# Bridge_Schem.net
KiCad netlist of a schematic drawn in Altium Designer
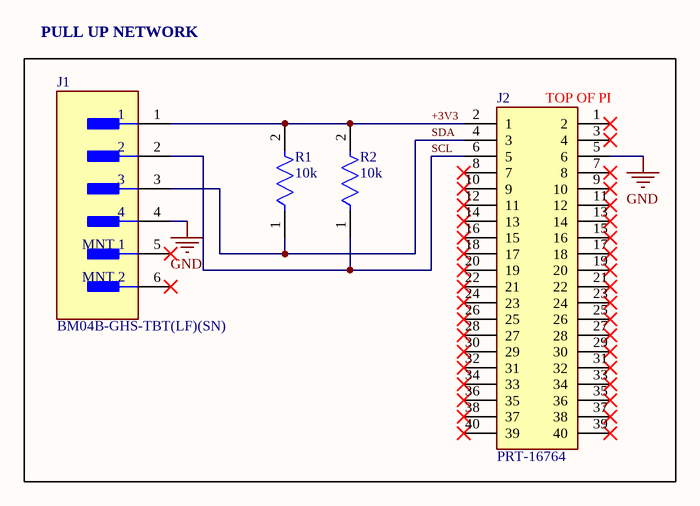
[diagram p0: Bridge_Schem.SchDoc]

(export (version "E")
  (design (tool "Eeschema 10.0.6"))
  (components
    (comp (ref "J1")
      (value "BM04B-GHS-TBT(LF)(SN)")
      (footprint "FP-BM04B-GHS-TBT_LF_SN-MFG")
      (description "CONN HEADER SMD 4POS 1.25MM")
      (fields (field (name "CHECK CONNECTOR") "Pending"))
      (libsource (lib "Altium Content Vault") (part "8e3688c4b118bffc0dd9b7401e414ba"))
    )
    (comp (ref "J2")
      (value "PRT-16764")
      (footprint "SamacSys:RHDR40W64P254_2X20_5130X500X1375P")
      (description "Connector")
      (fields (field (name "MOUSER PART NUMBER") "474-PRT-16764"))
      (libsource (lib "*") (part "PRT-16764"))
    )
    (comp (ref "R1")
      (value "10k")
      (footprint "FP-AT0805-MFG")
      (description "Thin Film Chip Resistors Automotive Grade 10kΩ 0.5% 50ppm/°C 0805")
      (fields (field (name "TOLERANCE") "0.5%"))
      (libsource (lib "Altium Content Vault") (part "1029c3af85768c4190bb7ad29bc67b5"))
    )
    (comp (ref "R2")
      (value "10k")
      (footprint "FP-AT0805-MFG")
      (description "Thin Film Chip Resistors Automotive Grade 10kΩ 0.5% 50ppm/°C 0805")
      (fields (field (name "TOLERANCE") "0.5%"))
      (libsource (lib "Altium Content Vault") (part "1029c3af85768c4190bb7ad29bc67b5"))
    )
  )
  (nets
    (net (code "1") (name "/+3V3") (class "Default")
      (node (ref "J1") (pin "1") (pinfunction "1_1") (pintype "passive"))
      (node (ref "J2") (pin "2") (pinfunction "1_2") (pintype "passive"))
      (node (ref "R1") (pin "2") (pinfunction "2_2") (pintype "passive"))
      (node (ref "R2") (pin "2") (pinfunction "2_2") (pintype "passive"))
    )
    (net (code "2") (name "/SCL") (class "Default")
      (node (ref "J1") (pin "2") (pinfunction "2_2") (pintype "passive"))
      (node (ref "J2") (pin "6") (pinfunction "5_6") (pintype "passive"))
      (node (ref "R2") (pin "1") (pinfunction "1_1") (pintype "passive"))
    )
    (net (code "3") (name "/SDA") (class "Default")
      (node (ref "J1") (pin "3") (pinfunction "3_3") (pintype "passive"))
      (node (ref "J2") (pin "4") (pinfunction "3_4") (pintype "passive"))
      (node (ref "R1") (pin "1") (pinfunction "1_1") (pintype "passive"))
    )
    (net (code "4") (name "GND") (class "Default")
      (node (ref "J1") (pin "4") (pinfunction "4_4") (pintype "passive"))
      (node (ref "J2") (pin "5") (pinfunction "6_5") (pintype "passive"))
    )
    (net (code "5") (name "unconnected-(J1-MNT_1-Pad5)") (class "Default")
      (node (ref "J1") (pin "5") (pinfunction "MNT_1_5") (pintype "passive+no_connect"))
    )
    (net (code "6") (name "unconnected-(J1-MNT_2-Pad6)") (class "Default")
      (node (ref "J1") (pin "6") (pinfunction "MNT_2_6") (pintype "passive+no_connect"))
    )
    (net (code "7") (name "unconnected-(J2-2-Pad1)") (class "Default")
      (node (ref "J2") (pin "1") (pinfunction "2_1") (pintype "passive+no_connect"))
    )
    (net (code "8") (name "unconnected-(J2-4-Pad3)") (class "Default")
      (node (ref "J2") (pin "3") (pinfunction "4_3") (pintype "passive+no_connect"))
    )
    (net (code "9") (name "unconnected-(J2-7-Pad8)") (class "Default")
      (node (ref "J2") (pin "8") (pinfunction "7_8") (pintype "passive+no_connect"))
    )
    (net (code "10") (name "unconnected-(J2-8-Pad7)") (class "Default")
      (node (ref "J2") (pin "7") (pinfunction "8_7") (pintype "passive+no_connect"))
    )
    (net (code "11") (name "unconnected-(J2-9-Pad10)") (class "Default")
      (node (ref "J2") (pin "10") (pinfunction "9_10") (pintype "passive+no_connect"))
    )
    (net (code "12") (name "unconnected-(J2-10-Pad9)") (class "Default")
      (node (ref "J2") (pin "9") (pinfunction "10_9") (pintype "passive+no_connect"))
    )
    (net (code "13") (name "unconnected-(J2-11-Pad12)") (class "Default")
      (node (ref "J2") (pin "12") (pinfunction "11_12") (pintype "passive+no_connect"))
    )
    (net (code "14") (name "unconnected-(J2-12-Pad11)") (class "Default")
      (node (ref "J2") (pin "11") (pinfunction "12_11") (pintype "passive+no_connect"))
    )
    (net (code "15") (name "unconnected-(J2-13-Pad14)") (class "Default")
      (node (ref "J2") (pin "14") (pinfunction "13_14") (pintype "passive+no_connect"))
    )
    (net (code "16") (name "unconnected-(J2-14-Pad13)") (class "Default")
      (node (ref "J2") (pin "13") (pinfunction "14_13") (pintype "passive+no_connect"))
    )
    (net (code "17") (name "unconnected-(J2-15-Pad16)") (class "Default")
      (node (ref "J2") (pin "16") (pinfunction "15_16") (pintype "passive+no_connect"))
    )
    (net (code "18") (name "unconnected-(J2-16-Pad15)") (class "Default")
      (node (ref "J2") (pin "15") (pinfunction "16_15") (pintype "passive+no_connect"))
    )
    (net (code "19") (name "unconnected-(J2-17-Pad18)") (class "Default")
      (node (ref "J2") (pin "18") (pinfunction "17_18") (pintype "passive+no_connect"))
    )
    (net (code "20") (name "unconnected-(J2-18-Pad17)") (class "Default")
      (node (ref "J2") (pin "17") (pinfunction "18_17") (pintype "passive+no_connect"))
    )
    (net (code "21") (name "unconnected-(J2-19-Pad20)") (class "Default")
      (node (ref "J2") (pin "20") (pinfunction "19_20") (pintype "passive+no_connect"))
    )
    (net (code "22") (name "unconnected-(J2-20-Pad19)") (class "Default")
      (node (ref "J2") (pin "19") (pinfunction "20_19") (pintype "passive+no_connect"))
    )
    (net (code "23") (name "unconnected-(J2-21-Pad22)") (class "Default")
      (node (ref "J2") (pin "22") (pinfunction "21_22") (pintype "passive+no_connect"))
    )
    (net (code "24") (name "unconnected-(J2-22-Pad21)") (class "Default")
      (node (ref "J2") (pin "21") (pinfunction "22_21") (pintype "passive+no_connect"))
    )
    (net (code "25") (name "unconnected-(J2-23-Pad24)") (class "Default")
      (node (ref "J2") (pin "24") (pinfunction "23_24") (pintype "passive+no_connect"))
    )
    (net (code "26") (name "unconnected-(J2-24-Pad23)") (class "Default")
      (node (ref "J2") (pin "23") (pinfunction "24_23") (pintype "passive+no_connect"))
    )
    (net (code "27") (name "unconnected-(J2-25-Pad26)") (class "Default")
      (node (ref "J2") (pin "26") (pinfunction "25_26") (pintype "passive+no_connect"))
    )
    (net (code "28") (name "unconnected-(J2-26-Pad25)") (class "Default")
      (node (ref "J2") (pin "25") (pinfunction "26_25") (pintype "passive+no_connect"))
    )
    (net (code "29") (name "unconnected-(J2-27-Pad28)") (class "Default")
      (node (ref "J2") (pin "28") (pinfunction "27_28") (pintype "passive+no_connect"))
    )
    (net (code "30") (name "unconnected-(J2-28-Pad27)") (class "Default")
      (node (ref "J2") (pin "27") (pinfunction "28_27") (pintype "passive+no_connect"))
    )
    (net (code "31") (name "unconnected-(J2-29-Pad30)") (class "Default")
      (node (ref "J2") (pin "30") (pinfunction "29_30") (pintype "passive+no_connect"))
    )
    (net (code "32") (name "unconnected-(J2-30-Pad29)") (class "Default")
      (node (ref "J2") (pin "29") (pinfunction "30_29") (pintype "passive+no_connect"))
    )
    (net (code "33") (name "unconnected-(J2-31-Pad32)") (class "Default")
      (node (ref "J2") (pin "32") (pinfunction "31_32") (pintype "passive+no_connect"))
    )
    (net (code "34") (name "unconnected-(J2-32-Pad31)") (class "Default")
      (node (ref "J2") (pin "31") (pinfunction "32_31") (pintype "passive+no_connect"))
    )
    (net (code "35") (name "unconnected-(J2-33-Pad34)") (class "Default")
      (node (ref "J2") (pin "34") (pinfunction "33_34") (pintype "passive+no_connect"))
    )
    (net (code "36") (name "unconnected-(J2-34-Pad33)") (class "Default")
      (node (ref "J2") (pin "33") (pinfunction "34_33") (pintype "passive+no_connect"))
    )
    (net (code "37") (name "unconnected-(J2-35-Pad36)") (class "Default")
      (node (ref "J2") (pin "36") (pinfunction "35_36") (pintype "passive+no_connect"))
    )
    (net (code "38") (name "unconnected-(J2-36-Pad35)") (class "Default")
      (node (ref "J2") (pin "35") (pinfunction "36_35") (pintype "passive+no_connect"))
    )
    (net (code "39") (name "unconnected-(J2-37-Pad38)") (class "Default")
      (node (ref "J2") (pin "38") (pinfunction "37_38") (pintype "passive+no_connect"))
    )
    (net (code "40") (name "unconnected-(J2-38-Pad37)") (class "Default")
      (node (ref "J2") (pin "37") (pinfunction "38_37") (pintype "passive+no_connect"))
    )
    (net (code "41") (name "unconnected-(J2-39-Pad40)") (class "Default")
      (node (ref "J2") (pin "40") (pinfunction "39_40") (pintype "passive+no_connect"))
    )
    (net (code "42") (name "unconnected-(J2-40-Pad39)") (class "Default")
      (node (ref "J2") (pin "39") (pinfunction "40_39") (pintype "passive+no_connect"))
    )
  )
)
